# openSipPuff_rev_B.net
KiCad netlist of a schematic drawn in EAGLE
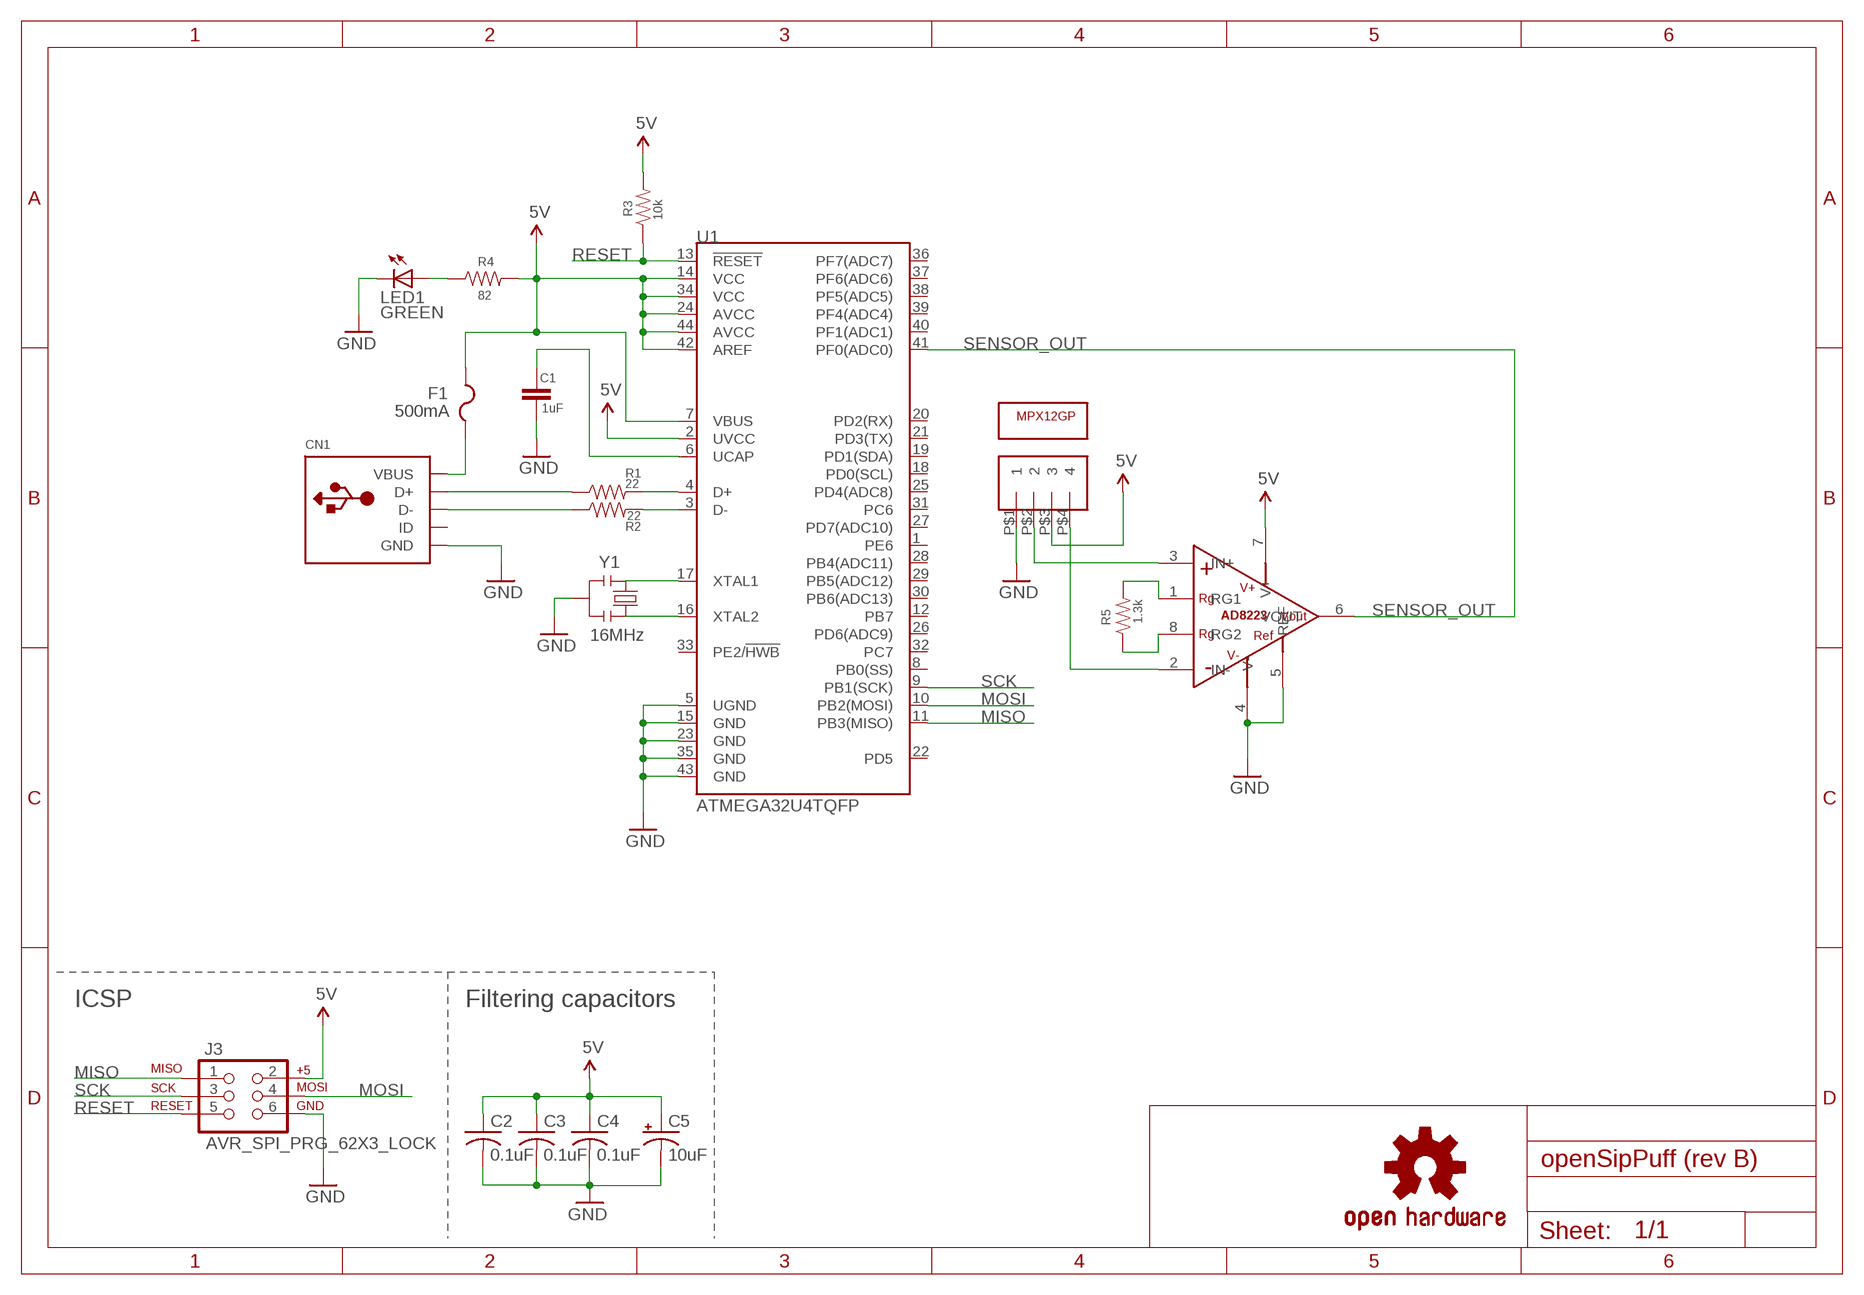
[diagram p0: schematic, sheet 1]

(export (version "E")
  (design (tool "Eeschema 10.0.6"))
  (components
    (comp (ref "C1")
      (value "1uF")
      (footprint "eagle-import:0805")
      (libsource (lib "eagle-import") (part "CAP0805"))
    )
    (comp (ref "C2")
      (value "0.1uF")
      (footprint "eagle-import:C0805K")
      (libsource (lib "eagle-import") (part "C-USC0805K"))
    )
    (comp (ref "C3")
      (value "0.1uF")
      (footprint "eagle-import:C0805K")
      (libsource (lib "eagle-import") (part "C-USC0805K"))
    )
    (comp (ref "C4")
      (value "0.1uF")
      (footprint "eagle-import:C0805K")
      (libsource (lib "eagle-import") (part "C-USC0805K"))
    )
    (comp (ref "C5")
      (value "10uF")
      (footprint "eagle-import:A_3216-18R")
      (libsource (lib "eagle-import") (part "CPOL-USA/3216-18R"))
    )
    (comp (ref "CN1")
      (value "USBMOLEX")
      (footprint "eagle-import:USB-MINIB-THM-MOLEX")
      (libsource (lib "eagle-import") (part "USBMOLEX"))
    )
    (comp (ref "F1")
      (value "500mA")
      (footprint "eagle-import:R1206")
      (libsource (lib "eagle-import") (part "PTCFUSE-1206"))
    )
    (comp (ref "J2")
      (value "1X04-RA")
      (footprint "eagle-import:1X04-RA")
      (libsource (lib "eagle-import") (part "1X04-RA"))
    )
    (comp (ref "J3")
      (value "AVR_SPI_PRG_62X3_LOCK")
      (footprint "eagle-import:2X3_LOCK")
      (libsource (lib "eagle-import") (part "AVR_SPI_PRG_62X3_LOCK"))
    )
    (comp (ref "LED1")
      (value "GREEN")
      (footprint "eagle-import:CHIPLED_0805")
      (libsource (lib "eagle-import") (part "LEDCHIPLED_0805"))
    )
    (comp (ref "LOGO1")
      (value "OSHW-LOGOM")
      (footprint "eagle-import:OSHW-LOGO-M")
      (libsource (lib "eagle-import") (part "OSHW-LOGOM"))
    )
    (comp (ref "R1")
      (value "22")
      (footprint "eagle-import:0805")
      (libsource (lib "eagle-import") (part "RESISTOR0805-RES"))
    )
    (comp (ref "R2")
      (value "22")
      (footprint "eagle-import:0805")
      (libsource (lib "eagle-import") (part "RESISTOR0805-RES"))
    )
    (comp (ref "R3")
      (value "10k")
      (footprint "eagle-import:0805")
      (libsource (lib "eagle-import") (part "RESISTOR0805-RES"))
    )
    (comp (ref "R4")
      (value "82")
      (footprint "eagle-import:0805")
      (libsource (lib "eagle-import") (part "RESISTOR0805-RES"))
    )
    (comp (ref "R5")
      (value "1.3k")
      (footprint "eagle-import:0805")
      (libsource (lib "eagle-import") (part "RESISTOR0805-RES"))
    )
    (comp (ref "U1")
      (value "ATMEGA32U4TQFP")
      (footprint "eagle-import:SPARKFUN-DIGITALIC_TQFP44")
      (libsource (lib "eagle-import") (part "ATMEGA32U4TQFP"))
    )
    (comp (ref "U2")
      (value "AD8223")
      (footprint "eagle-import:MSOP-8")
      (libsource (lib "eagle-import") (part "AD8223"))
    )
    (comp (ref "U3")
      (value "MPX12GP")
      (footprint "eagle-import:MPX12GP")
      (libsource (lib "eagle-import") (part "MPX12GP"))
    )
    (comp (ref "Y1")
      (value "16MHz")
      (footprint "eagle-import:RESONATOR-PTH")
      (libsource (lib "eagle-import") (part "RESONATORPTH"))
    )
  )
  (nets
    (net (code "1") (name "/MISO") (class "Default")
      (node (ref "J3") (pin "1") (pinfunction "1_1") (pintype "passive"))
      (node (ref "U1") (pin "11") (pinfunction "PB3(MISO)_11") (pintype "bidirectional"))
    )
    (net (code "2") (name "/MOSI") (class "Default")
      (node (ref "J3") (pin "4") (pinfunction "4_4") (pintype "passive"))
      (node (ref "U1") (pin "10") (pinfunction "PB2(MOSI)_10") (pintype "bidirectional"))
    )
    (net (code "3") (name "/RESET") (class "Default")
      (node (ref "J3") (pin "5") (pinfunction "5_5") (pintype "passive"))
      (node (ref "R3") (pin "1") (pinfunction "1_1") (pintype "passive"))
      (node (ref "U1") (pin "13") (pinfunction "~{RESET}_13") (pintype "bidirectional"))
    )
    (net (code "4") (name "/SCK") (class "Default")
      (node (ref "J3") (pin "3") (pinfunction "3_3") (pintype "passive"))
      (node (ref "U1") (pin "9") (pinfunction "PB1(SCK)_9") (pintype "bidirectional"))
    )
    (net (code "5") (name "/SENSOR_OUT") (class "Default")
      (node (ref "U1") (pin "41") (pinfunction "PF0(ADC0)_41") (pintype "bidirectional"))
      (node (ref "U2") (pin "6") (pinfunction "VOUT_6") (pintype "output"))
    )
    (net (code "6") (name "5V") (class "Default")
      (node (ref "C2") (pin "1") (pinfunction "1_1") (pintype "passive"))
      (node (ref "C3") (pin "1") (pinfunction "1_1") (pintype "passive"))
      (node (ref "C4") (pin "1") (pinfunction "1_1") (pintype "passive"))
      (node (ref "C5") (pin "+") (pinfunction "+_+") (pintype "passive"))
      (node (ref "F1") (pin "2") (pinfunction "2_2") (pintype "passive"))
      (node (ref "J2") (pin "P$3") (pinfunction "3_P$3") (pintype "power_in"))
      (node (ref "J3") (pin "2") (pinfunction "2_2") (pintype "passive"))
      (node (ref "R3") (pin "2") (pinfunction "2_2") (pintype "passive"))
      (node (ref "R4") (pin "2") (pinfunction "2_2") (pintype "passive"))
      (node (ref "U1") (pin "14") (pinfunction "VCC_14") (pintype "bidirectional"))
      (node (ref "U1") (pin "2") (pinfunction "UVCC_2") (pintype "bidirectional"))
      (node (ref "U1") (pin "24") (pinfunction "AVCC_24") (pintype "bidirectional"))
      (node (ref "U1") (pin "34") (pinfunction "VCC_34") (pintype "bidirectional"))
      (node (ref "U1") (pin "42") (pinfunction "AREF_42") (pintype "bidirectional"))
      (node (ref "U1") (pin "44") (pinfunction "AVCC_44") (pintype "bidirectional"))
      (node (ref "U1") (pin "7") (pinfunction "VBUS_7") (pintype "bidirectional"))
      (node (ref "U2") (pin "7") (pinfunction "V+_7") (pintype "power_in"))
    )
    (net (code "7") (name "GND") (class "Default")
      (node (ref "C1") (pin "2") (pinfunction "2_2") (pintype "passive"))
      (node (ref "C2") (pin "2") (pinfunction "2_2") (pintype "passive"))
      (node (ref "C3") (pin "2") (pinfunction "2_2") (pintype "passive"))
      (node (ref "C4") (pin "2") (pinfunction "2_2") (pintype "passive"))
      (node (ref "C5") (pin "-") (pinfunction "-_-") (pintype "passive"))
      (node (ref "CN1") (pin "GND") (pinfunction "GND_GND") (pintype "power_in"))
      (node (ref "J2") (pin "P$1") (pinfunction "1_P$1") (pintype "power_in"))
      (node (ref "J3") (pin "6") (pinfunction "6_6") (pintype "passive"))
      (node (ref "LED1") (pin "C") (pinfunction "C_C") (pintype "passive"))
      (node (ref "U1") (pin "15") (pinfunction "GND_15") (pintype "bidirectional"))
      (node (ref "U1") (pin "23") (pinfunction "GND_23") (pintype "bidirectional"))
      (node (ref "U1") (pin "35") (pinfunction "GND_35") (pintype "bidirectional"))
      (node (ref "U1") (pin "43") (pinfunction "GND_43") (pintype "bidirectional"))
      (node (ref "U1") (pin "5") (pinfunction "UGND_5") (pintype "bidirectional"))
      (node (ref "U2") (pin "4") (pinfunction "V-_4") (pintype "power_in"))
      (node (ref "U2") (pin "5") (pinfunction "REF_5") (pintype "bidirectional"))
      (node (ref "Y1") (pin "2") (pinfunction "2_2") (pintype "passive"))
    )
    (net (code "8") (name "Net-(CN1-PadD+)") (class "Default")
      (node (ref "CN1") (pin "D+") (pinfunction "D+_D+") (pintype "bidirectional"))
      (node (ref "R1") (pin "1") (pinfunction "1_1") (pintype "passive"))
    )
    (net (code "9") (name "Net-(CN1-PadD-)") (class "Default")
      (node (ref "CN1") (pin "D-") (pinfunction "D-_D-") (pintype "bidirectional"))
      (node (ref "R2") (pin "1") (pinfunction "1_1") (pintype "passive"))
    )
    (net (code "10") (name "Net-(CN1-PadVBUS)") (class "Default")
      (node (ref "CN1") (pin "VBUS") (pinfunction "VBUS_VBUS") (pintype "power_in"))
      (node (ref "F1") (pin "1") (pinfunction "1_1") (pintype "passive"))
    )
    (net (code "11") (name "Net-(J2-2)") (class "Default")
      (node (ref "J2") (pin "P$2") (pinfunction "2_P$2") (pintype "output"))
      (node (ref "U2") (pin "3") (pinfunction "IN+_3") (pintype "input"))
    )
    (net (code "12") (name "Net-(J2-4)") (class "Default")
      (node (ref "J2") (pin "P$4") (pinfunction "4_P$4") (pintype "output"))
      (node (ref "U2") (pin "2") (pinfunction "IN-_2") (pintype "input"))
    )
    (net (code "13") (name "Net-(LED1-PadA)") (class "Default")
      (node (ref "LED1") (pin "A") (pinfunction "A_A") (pintype "passive"))
      (node (ref "R4") (pin "1") (pinfunction "1_1") (pintype "passive"))
    )
    (net (code "14") (name "Net-(U1-D+)") (class "Default")
      (node (ref "R1") (pin "2") (pinfunction "2_2") (pintype "passive"))
      (node (ref "U1") (pin "4") (pinfunction "D+_4") (pintype "bidirectional"))
    )
    (net (code "15") (name "Net-(U1-D-)") (class "Default")
      (node (ref "R2") (pin "2") (pinfunction "2_2") (pintype "passive"))
      (node (ref "U1") (pin "3") (pinfunction "D-_3") (pintype "bidirectional"))
    )
    (net (code "16") (name "Net-(U1-UCAP)") (class "Default")
      (node (ref "C1") (pin "1") (pinfunction "1_1") (pintype "passive"))
      (node (ref "U1") (pin "6") (pinfunction "UCAP_6") (pintype "bidirectional"))
    )
    (net (code "17") (name "Net-(U1-XTAL1)") (class "Default")
      (node (ref "U1") (pin "17") (pinfunction "XTAL1_17") (pintype "bidirectional"))
      (node (ref "Y1") (pin "1") (pinfunction "1_1") (pintype "passive"))
    )
    (net (code "18") (name "Net-(U1-XTAL2)") (class "Default")
      (node (ref "U1") (pin "16") (pinfunction "XTAL2_16") (pintype "bidirectional"))
      (node (ref "Y1") (pin "3") (pinfunction "3_3") (pintype "passive"))
    )
    (net (code "19") (name "Net-(U2-RG1)") (class "Default")
      (node (ref "R5") (pin "2") (pinfunction "2_2") (pintype "passive"))
      (node (ref "U2") (pin "1") (pinfunction "RG1_1") (pintype "input"))
    )
    (net (code "20") (name "Net-(U2-RG2)") (class "Default")
      (node (ref "R5") (pin "1") (pinfunction "1_1") (pintype "passive"))
      (node (ref "U2") (pin "8") (pinfunction "RG2_8") (pintype "input"))
    )
    (net (code "21") (name "unconnected-(CN1-PadID)") (class "Default")
      (node (ref "CN1") (pin "ID") (pinfunction "ID_ID") (pintype "bidirectional"))
    )
    (net (code "22") (name "unconnected-(U1-PB0(SS)-Pad8)") (class "Default")
      (node (ref "U1") (pin "8") (pinfunction "PB0(SS)_8") (pintype "bidirectional"))
    )
    (net (code "23") (name "unconnected-(U1-PB4(ADC11)-Pad28)") (class "Default")
      (node (ref "U1") (pin "28") (pinfunction "PB4(ADC11)_28") (pintype "bidirectional"))
    )
    (net (code "24") (name "unconnected-(U1-PB5(ADC12)-Pad29)") (class "Default")
      (node (ref "U1") (pin "29") (pinfunction "PB5(ADC12)_29") (pintype "bidirectional"))
    )
    (net (code "25") (name "unconnected-(U1-PB6(ADC13)-Pad30)") (class "Default")
      (node (ref "U1") (pin "30") (pinfunction "PB6(ADC13)_30") (pintype "bidirectional"))
    )
    (net (code "26") (name "unconnected-(U1-PB7-Pad12)") (class "Default")
      (node (ref "U1") (pin "12") (pinfunction "PB7_12") (pintype "bidirectional"))
    )
    (net (code "27") (name "unconnected-(U1-PC6-Pad31)") (class "Default")
      (node (ref "U1") (pin "31") (pinfunction "PC6_31") (pintype "bidirectional"))
    )
    (net (code "28") (name "unconnected-(U1-PC7-Pad32)") (class "Default")
      (node (ref "U1") (pin "32") (pinfunction "PC7_32") (pintype "bidirectional"))
    )
    (net (code "29") (name "unconnected-(U1-PD0(SCL)-Pad18)") (class "Default")
      (node (ref "U1") (pin "18") (pinfunction "PD0(SCL)_18") (pintype "bidirectional"))
    )
    (net (code "30") (name "unconnected-(U1-PD1(SDA)-Pad19)") (class "Default")
      (node (ref "U1") (pin "19") (pinfunction "PD1(SDA)_19") (pintype "bidirectional"))
    )
    (net (code "31") (name "unconnected-(U1-PD2(RX)-Pad20)") (class "Default")
      (node (ref "U1") (pin "20") (pinfunction "PD2(RX)_20") (pintype "bidirectional"))
    )
    (net (code "32") (name "unconnected-(U1-PD3(TX)-Pad21)") (class "Default")
      (node (ref "U1") (pin "21") (pinfunction "PD3(TX)_21") (pintype "bidirectional"))
    )
    (net (code "33") (name "unconnected-(U1-PD4(ADC8)-Pad25)") (class "Default")
      (node (ref "U1") (pin "25") (pinfunction "PD4(ADC8)_25") (pintype "bidirectional"))
    )
    (net (code "34") (name "unconnected-(U1-PD5-Pad22)") (class "Default")
      (node (ref "U1") (pin "22") (pinfunction "PD5_22") (pintype "bidirectional"))
    )
    (net (code "35") (name "unconnected-(U1-PD6(ADC9)-Pad26)") (class "Default")
      (node (ref "U1") (pin "26") (pinfunction "PD6(ADC9)_26") (pintype "bidirectional"))
    )
    (net (code "36") (name "unconnected-(U1-PD7(ADC10)-Pad27)") (class "Default")
      (node (ref "U1") (pin "27") (pinfunction "PD7(ADC10)_27") (pintype "bidirectional"))
    )
    (net (code "37") (name "unconnected-(U1-PE2{slash}~{HWB}-Pad33)") (class "Default")
      (node (ref "U1") (pin "33") (pinfunction "PE2/~{HWB}_33") (pintype "bidirectional"))
    )
    (net (code "38") (name "unconnected-(U1-PE6-Pad1)") (class "Default")
      (node (ref "U1") (pin "1") (pinfunction "PE6_1") (pintype "bidirectional"))
    )
    (net (code "39") (name "unconnected-(U1-PF1(ADC1)-Pad40)") (class "Default")
      (node (ref "U1") (pin "40") (pinfunction "PF1(ADC1)_40") (pintype "bidirectional"))
    )
    (net (code "40") (name "unconnected-(U1-PF4(ADC4)-Pad39)") (class "Default")
      (node (ref "U1") (pin "39") (pinfunction "PF4(ADC4)_39") (pintype "bidirectional"))
    )
    (net (code "41") (name "unconnected-(U1-PF5(ADC5)-Pad38)") (class "Default")
      (node (ref "U1") (pin "38") (pinfunction "PF5(ADC5)_38") (pintype "bidirectional"))
    )
    (net (code "42") (name "unconnected-(U1-PF6(ADC6)-Pad37)") (class "Default")
      (node (ref "U1") (pin "37") (pinfunction "PF6(ADC6)_37") (pintype "bidirectional"))
    )
    (net (code "43") (name "unconnected-(U1-PF7(ADC7)-Pad36)") (class "Default")
      (node (ref "U1") (pin "36") (pinfunction "PF7(ADC7)_36") (pintype "bidirectional"))
    )
  )
)
